# MPU.net
KiCad netlist of a schematic drawn in Altium Designer
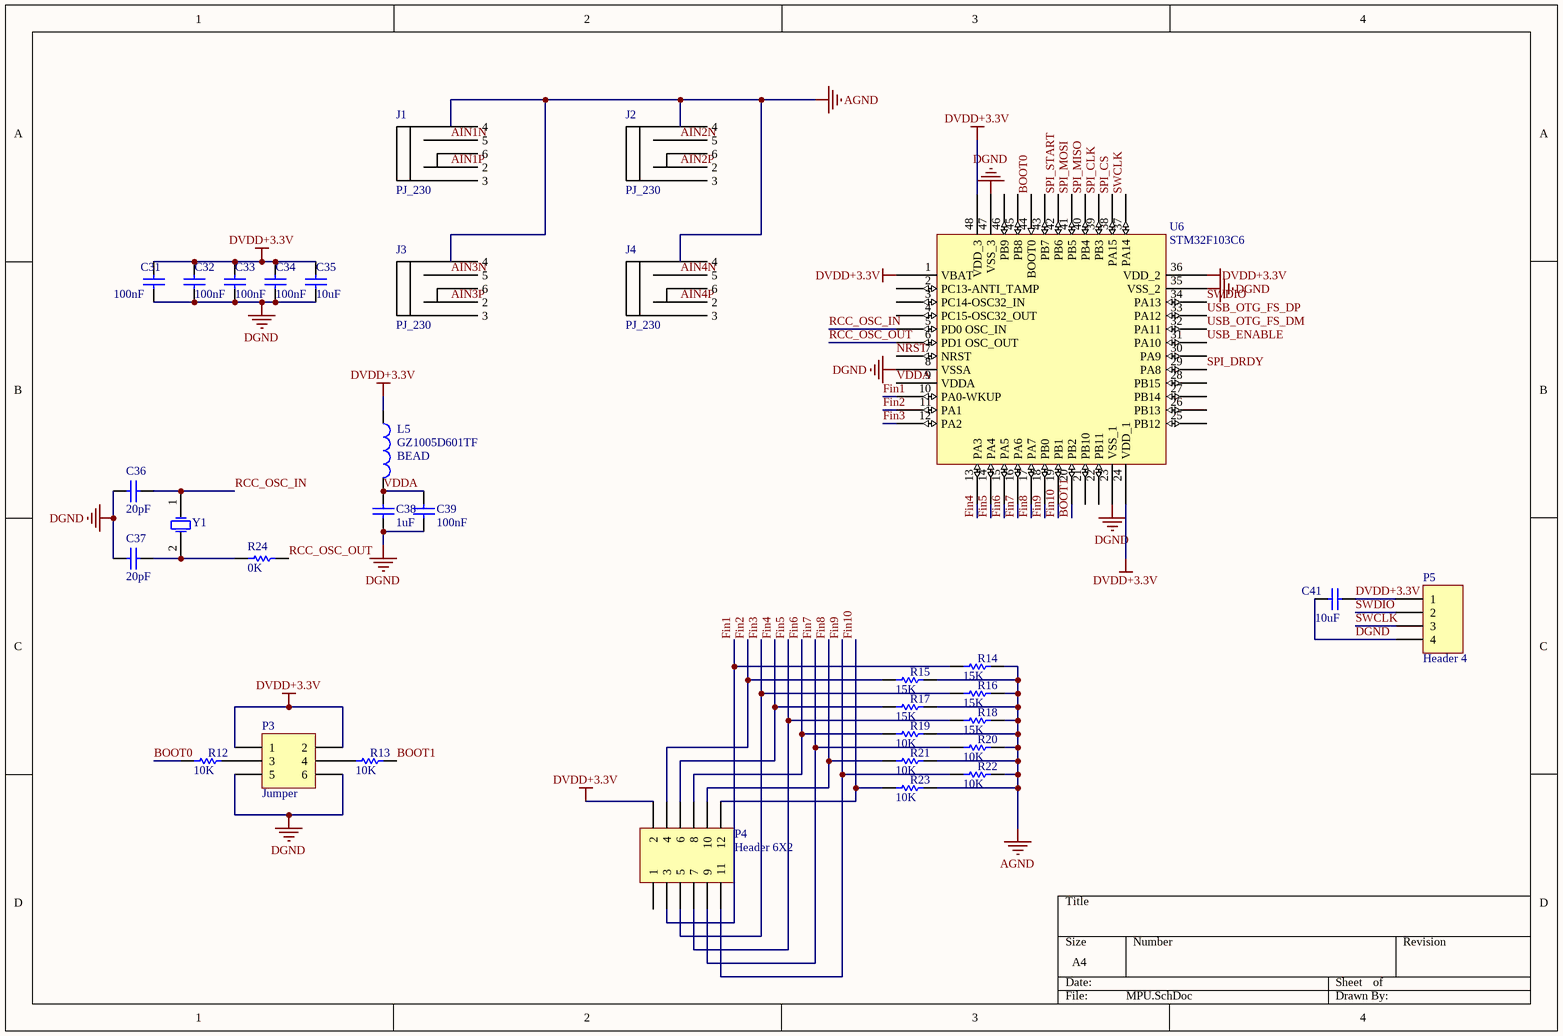
[diagram p0: MPU.SchDoc]

(export (version "E")
  (design (tool "Eeschema 10.0.6"))
  (components
    (comp (ref "C31")
      (value "100nF")
      (footprint "1608[0603]")
      (description "Capacitor")
      (fields (field (name "PUBLISHER") "Altium Limited"))
      (libsource (lib "Miscellaneous Devices") (part "Cap"))
    )
    (comp (ref "C32")
      (value "100nF")
      (footprint "1608[0603]")
      (description "Capacitor")
      (fields (field (name "PUBLISHER") "Altium Limited"))
      (libsource (lib "Miscellaneous Devices") (part "Cap"))
    )
    (comp (ref "C33")
      (value "100nF")
      (footprint "1608[0603]")
      (description "Capacitor")
      (fields (field (name "PUBLISHER") "Altium Limited"))
      (libsource (lib "Miscellaneous Devices") (part "Cap"))
    )
    (comp (ref "C34")
      (value "100nF")
      (footprint "1608[0603]")
      (description "Capacitor")
      (fields (field (name "PUBLISHER") "Altium Limited"))
      (libsource (lib "Miscellaneous Devices") (part "Cap"))
    )
    (comp (ref "C35")
      (value "10uF")
      (footprint "1608[0603]")
      (description "Capacitor")
      (fields (field (name "PUBLISHER") "Altium Limited"))
      (libsource (lib "Miscellaneous Devices") (part "Cap"))
    )
    (comp (ref "C36")
      (value "20pF")
      (footprint "1608[0603]")
      (description "Capacitor")
      (fields (field (name "PUBLISHER") "Altium Limited"))
      (libsource (lib "Miscellaneous Devices") (part "Cap"))
    )
    (comp (ref "C37")
      (value "20pF")
      (footprint "1608[0603]")
      (description "Capacitor")
      (fields (field (name "PUBLISHER") "Altium Limited"))
      (libsource (lib "Miscellaneous Devices") (part "Cap"))
    )
    (comp (ref "C38")
      (value "1uF")
      (footprint "1608[0603]")
      (description "Capacitor")
      (fields (field (name "PUBLISHER") "Altium Limited"))
      (libsource (lib "Miscellaneous Devices") (part "Cap"))
    )
    (comp (ref "C39")
      (value "100nF")
      (footprint "1608[0603]")
      (description "Capacitor")
      (fields (field (name "PUBLISHER") "Altium Limited"))
      (libsource (lib "Miscellaneous Devices") (part "Cap"))
    )
    (comp (ref "C41")
      (value "10uF")
      (footprint "1608[0603]")
      (description "Capacitor")
      (fields (field (name "PUBLISHER") "Altium Limited"))
      (libsource (lib "Miscellaneous Devices") (part "Cap"))
    )
    (comp (ref "J1")
      (value "PJ_230")
      (footprint "PJ_230")
      (description "Phone Jack")
      (libsource (lib "PJ_230") (part "PJ_230"))
    )
    (comp (ref "J2")
      (value "PJ_230")
      (footprint "PJ_230")
      (description "Phone Jack")
      (libsource (lib "PJ_230") (part "PJ_230"))
    )
    (comp (ref "J3")
      (value "PJ_230")
      (footprint "PJ_230")
      (description "Phone Jack")
      (libsource (lib "PJ_230") (part "PJ_230"))
    )
    (comp (ref "J4")
      (value "PJ_230")
      (footprint "PJ_230")
      (description "Phone Jack")
      (libsource (lib "PJ_230") (part "PJ_230"))
    )
    (comp (ref "L5")
      (value "GZ1005D601TF")
      (footprint "0402-A")
      (description "Inductor")
      (fields (field (name "PUBLISHER") "Altium Limited"))
      (libsource (lib "Miscellaneous Devices") (part "Inductor"))
    )
    (comp (ref "P3")
      (value "Jumper")
      (footprint "HDR2X3")
      (description "Header, 3-Pin, Dual row")
      (fields (field (name "PUBLISHER") "Altium Limited"))
      (libsource (lib "Miscellaneous Connectors") (part "Header 3X2"))
    )
    (comp (ref "P4")
      (value "Header 6X2")
      (footprint "HDR2X6")
      (description "Header, 6-Pin, Dual row")
      (fields (field (name "PUBLISHER") "Altium Limited"))
      (libsource (lib "Miscellaneous Connectors") (part "Header 6X2"))
    )
    (comp (ref "P5")
      (value "Header 4")
      (footprint "XH4")
      (description "Header, 4-Pin")
      (fields (field (name "PUBLISHER") "Altium Limited"))
      (libsource (lib "Miscellaneous Connectors") (part "Header 4"))
    )
    (comp (ref "R12")
      (value "10K")
      (footprint "J1-0603")
      (description "Resistor")
      (fields (field (name "PUBLISHER") "Altium Limited"))
      (libsource (lib "Miscellaneous Devices") (part "Res1"))
    )
    (comp (ref "R13")
      (value "10K")
      (footprint "J1-0603")
      (description "Resistor")
      (fields (field (name "PUBLISHER") "Altium Limited"))
      (libsource (lib "Miscellaneous Devices") (part "Res1"))
    )
    (comp (ref "R14")
      (value "15K")
      (footprint "J1-0603")
      (description "Resistor")
      (fields (field (name "PUBLISHER") "Altium Limited"))
      (libsource (lib "Miscellaneous Devices") (part "Res1"))
    )
    (comp (ref "R15")
      (value "15K")
      (footprint "J1-0603")
      (description "Resistor")
      (fields (field (name "PUBLISHER") "Altium Limited"))
      (libsource (lib "Miscellaneous Devices") (part "Res1"))
    )
    (comp (ref "R16")
      (value "15K")
      (footprint "J1-0603")
      (description "Resistor")
      (fields (field (name "PUBLISHER") "Altium Limited"))
      (libsource (lib "Miscellaneous Devices") (part "Res1"))
    )
    (comp (ref "R17")
      (value "15K")
      (footprint "J1-0603")
      (description "Resistor")
      (fields (field (name "PUBLISHER") "Altium Limited"))
      (libsource (lib "Miscellaneous Devices") (part "Res1"))
    )
    (comp (ref "R18")
      (value "15K")
      (footprint "J1-0603")
      (description "Resistor")
      (fields (field (name "PUBLISHER") "Altium Limited"))
      (libsource (lib "Miscellaneous Devices") (part "Res1"))
    )
    (comp (ref "R19")
      (value "10K")
      (footprint "J1-0603")
      (description "Resistor")
      (fields (field (name "PUBLISHER") "Altium Limited"))
      (libsource (lib "Miscellaneous Devices") (part "Res1"))
    )
    (comp (ref "R20")
      (value "10K")
      (footprint "J1-0603")
      (description "Resistor")
      (fields (field (name "PUBLISHER") "Altium Limited"))
      (libsource (lib "Miscellaneous Devices") (part "Res1"))
    )
    (comp (ref "R21")
      (value "10K")
      (footprint "J1-0603")
      (description "Resistor")
      (fields (field (name "PUBLISHER") "Altium Limited"))
      (libsource (lib "Miscellaneous Devices") (part "Res1"))
    )
    (comp (ref "R22")
      (value "10K")
      (footprint "J1-0603")
      (description "Resistor")
      (fields (field (name "PUBLISHER") "Altium Limited"))
      (libsource (lib "Miscellaneous Devices") (part "Res1"))
    )
    (comp (ref "R23")
      (value "10K")
      (footprint "J1-0603")
      (description "Resistor")
      (fields (field (name "PUBLISHER") "Altium Limited"))
      (libsource (lib "Miscellaneous Devices") (part "Res1"))
    )
    (comp (ref "R24")
      (value "0K")
      (footprint "J1-0603")
      (description "Resistor")
      (fields (field (name "PUBLISHER") "Altium Limited"))
      (libsource (lib "Miscellaneous Devices") (part "Res1"))
    )
    (comp (ref "U6")
      (value "STM32F103C6")
      (footprint "STM32F103C8T6")
      (description "IC MCU 32BIT 64KB FLASH 48LQFP")
      (libsource (lib "STM32F103C8T6") (part "STM32F103C8T6"))
    )
    (comp (ref "Y1")
      (value "XTAL")
      (footprint "Crystal_HCM49")
      (description "Crystal Oscillator")
      (fields (field (name "PUBLISHER") "Altium Limited"))
      (libsource (lib "Miscellaneous Devices") (part "XTAL"))
    )
  )
  (nets
    (net (code "1") (name "/AIN1N") (class "Default")
      (node (ref "J1") (pin "5") (pinfunction "5_5") (pintype "passive"))
    )
    (net (code "2") (name "/AIN1P") (class "Default")
      (node (ref "J1") (pin "2") (pinfunction "2_2") (pintype "passive"))
    )
    (net (code "3") (name "/AIN2N") (class "Default")
      (node (ref "J2") (pin "5") (pinfunction "5_5") (pintype "passive"))
    )
    (net (code "4") (name "/AIN2P") (class "Default")
      (node (ref "J2") (pin "2") (pinfunction "2_2") (pintype "passive"))
    )
    (net (code "5") (name "/AIN3N") (class "Default")
      (node (ref "J3") (pin "5") (pinfunction "5_5") (pintype "passive"))
    )
    (net (code "6") (name "/AIN3P") (class "Default")
      (node (ref "J3") (pin "2") (pinfunction "2_2") (pintype "passive"))
    )
    (net (code "7") (name "/AIN4N") (class "Default")
      (node (ref "J4") (pin "5") (pinfunction "5_5") (pintype "passive"))
    )
    (net (code "8") (name "/AIN4P") (class "Default")
      (node (ref "J4") (pin "2") (pinfunction "2_2") (pintype "passive"))
    )
    (net (code "9") (name "/BOOT0") (class "Default")
      (node (ref "R12") (pin "1") (pinfunction "1_1") (pintype "passive"))
      (node (ref "U6") (pin "44") (pinfunction "BOOT0_44") (pintype "input"))
    )
    (net (code "10") (name "/BOOT1") (class "Default")
      (node (ref "R13") (pin "2") (pinfunction "2_2") (pintype "passive"))
      (node (ref "U6") (pin "20") (pinfunction "PB2_20") (pintype "bidirectional"))
    )
    (net (code "11") (name "/Fin1") (class "Default")
      (node (ref "P4") (pin "3") (pinfunction "3_3") (pintype "passive"))
      (node (ref "R14") (pin "1") (pinfunction "1_1") (pintype "passive"))
      (node (ref "U6") (pin "10") (pinfunction "PA0-WKUP_10") (pintype "bidirectional"))
    )
    (net (code "12") (name "/Fin2") (class "Default")
      (node (ref "P4") (pin "4") (pinfunction "4_4") (pintype "passive"))
      (node (ref "R15") (pin "1") (pinfunction "1_1") (pintype "passive"))
      (node (ref "U6") (pin "11") (pinfunction "PA1_11") (pintype "bidirectional"))
    )
    (net (code "13") (name "/Fin3") (class "Default")
      (node (ref "P4") (pin "5") (pinfunction "5_5") (pintype "passive"))
      (node (ref "R16") (pin "1") (pinfunction "1_1") (pintype "passive"))
      (node (ref "U6") (pin "12") (pinfunction "PA2_12") (pintype "bidirectional"))
    )
    (net (code "14") (name "/Fin4") (class "Default")
      (node (ref "P4") (pin "6") (pinfunction "6_6") (pintype "passive"))
      (node (ref "R17") (pin "1") (pinfunction "1_1") (pintype "passive"))
      (node (ref "U6") (pin "13") (pinfunction "PA3_13") (pintype "bidirectional"))
    )
    (net (code "15") (name "/Fin5") (class "Default")
      (node (ref "P4") (pin "7") (pinfunction "7_7") (pintype "passive"))
      (node (ref "R18") (pin "1") (pinfunction "1_1") (pintype "passive"))
      (node (ref "U6") (pin "14") (pinfunction "PA4_14") (pintype "bidirectional"))
    )
    (net (code "16") (name "/Fin6") (class "Default")
      (node (ref "P4") (pin "8") (pinfunction "8_8") (pintype "passive"))
      (node (ref "R19") (pin "1") (pinfunction "1_1") (pintype "passive"))
      (node (ref "U6") (pin "15") (pinfunction "PA5_15") (pintype "bidirectional"))
    )
    (net (code "17") (name "/Fin7") (class "Default")
      (node (ref "P4") (pin "9") (pinfunction "9_9") (pintype "passive"))
      (node (ref "R20") (pin "1") (pinfunction "1_1") (pintype "passive"))
      (node (ref "U6") (pin "16") (pinfunction "PA6_16") (pintype "bidirectional"))
    )
    (net (code "18") (name "/Fin8") (class "Default")
      (node (ref "P4") (pin "10") (pinfunction "10_10") (pintype "passive"))
      (node (ref "R21") (pin "1") (pinfunction "1_1") (pintype "passive"))
      (node (ref "U6") (pin "17") (pinfunction "PA7_17") (pintype "bidirectional"))
    )
    (net (code "19") (name "/Fin9") (class "Default")
      (node (ref "P4") (pin "11") (pinfunction "11_11") (pintype "passive"))
      (node (ref "R22") (pin "1") (pinfunction "1_1") (pintype "passive"))
      (node (ref "U6") (pin "18") (pinfunction "PB0_18") (pintype "bidirectional"))
    )
    (net (code "20") (name "/Fin10") (class "Default")
      (node (ref "P4") (pin "12") (pinfunction "12_12") (pintype "passive"))
      (node (ref "R23") (pin "1") (pinfunction "1_1") (pintype "passive"))
      (node (ref "U6") (pin "19") (pinfunction "PB1_19") (pintype "bidirectional"))
    )
    (net (code "21") (name "/NRST") (class "Default")
      (node (ref "U6") (pin "7") (pinfunction "NRST_7") (pintype "bidirectional"))
    )
    (net (code "22") (name "/RCC_OSC_IN") (class "Default")
      (node (ref "C36") (pin "2") (pinfunction "2_2") (pintype "passive"))
      (node (ref "U6") (pin "5") (pinfunction "PD0_OSC_IN_5") (pintype "bidirectional"))
      (node (ref "Y1") (pin "1") (pinfunction "OSC1_1") (pintype "passive"))
    )
    (net (code "23") (name "/RCC_OSC_OUT") (class "Default")
      (node (ref "R24") (pin "2") (pinfunction "2_2") (pintype "passive"))
      (node (ref "U6") (pin "6") (pinfunction "PD1_OSC_OUT_6") (pintype "bidirectional"))
    )
    (net (code "24") (name "/SPI_CLK") (class "Default")
      (node (ref "U6") (pin "39") (pinfunction "PB3_39") (pintype "bidirectional"))
    )
    (net (code "25") (name "/SPI_CS") (class "Default")
      (node (ref "U6") (pin "38") (pinfunction "PA15_38") (pintype "bidirectional"))
    )
    (net (code "26") (name "/SPI_DRDY") (class "Default")
      (node (ref "U6") (pin "29") (pinfunction "PA8_29") (pintype "bidirectional"))
    )
    (net (code "27") (name "/SPI_MISO") (class "Default")
      (node (ref "U6") (pin "40") (pinfunction "PB4_40") (pintype "bidirectional"))
    )
    (net (code "28") (name "/SPI_MOSI") (class "Default")
      (node (ref "U6") (pin "41") (pinfunction "PB5_41") (pintype "bidirectional"))
    )
    (net (code "29") (name "/SPI_START") (class "Default")
      (node (ref "U6") (pin "42") (pinfunction "PB6_42") (pintype "bidirectional"))
    )
    (net (code "30") (name "/SWCLK") (class "Default")
      (node (ref "P5") (pin "3") (pinfunction "3_3") (pintype "passive"))
      (node (ref "U6") (pin "37") (pinfunction "PA14_37") (pintype "bidirectional"))
    )
    (net (code "31") (name "/SWDIO") (class "Default")
      (node (ref "P5") (pin "2") (pinfunction "2_2") (pintype "passive"))
      (node (ref "U6") (pin "34") (pinfunction "PA13_34") (pintype "bidirectional"))
    )
    (net (code "32") (name "/USB_ENABLE") (class "Default")
      (node (ref "U6") (pin "31") (pinfunction "PA10_31") (pintype "bidirectional"))
    )
    (net (code "33") (name "/USB_OTG_FS_DM") (class "Default")
      (node (ref "U6") (pin "32") (pinfunction "PA11_32") (pintype "bidirectional"))
    )
    (net (code "34") (name "/USB_OTG_FS_DP") (class "Default")
      (node (ref "U6") (pin "33") (pinfunction "PA12_33") (pintype "bidirectional"))
    )
    (net (code "35") (name "/VDDA") (class "Default")
      (node (ref "C38") (pin "2") (pinfunction "2_2") (pintype "passive"))
      (node (ref "C39") (pin "2") (pinfunction "2_2") (pintype "passive"))
      (node (ref "L5") (pin "2") (pinfunction "2_2") (pintype "passive"))
      (node (ref "U6") (pin "9") (pinfunction "VDDA_9") (pintype "power_in"))
    )
    (net (code "36") (name "AGND") (class "Default")
      (node (ref "J1") (pin "4") (pinfunction "4_4") (pintype "passive"))
      (node (ref "J2") (pin "4") (pinfunction "4_4") (pintype "passive"))
      (node (ref "J3") (pin "4") (pinfunction "4_4") (pintype "passive"))
      (node (ref "J4") (pin "4") (pinfunction "4_4") (pintype "passive"))
      (node (ref "R14") (pin "2") (pinfunction "2_2") (pintype "passive"))
      (node (ref "R15") (pin "2") (pinfunction "2_2") (pintype "passive"))
      (node (ref "R16") (pin "2") (pinfunction "2_2") (pintype "passive"))
      (node (ref "R17") (pin "2") (pinfunction "2_2") (pintype "passive"))
      (node (ref "R18") (pin "2") (pinfunction "2_2") (pintype "passive"))
      (node (ref "R19") (pin "2") (pinfunction "2_2") (pintype "passive"))
      (node (ref "R20") (pin "2") (pinfunction "2_2") (pintype "passive"))
      (node (ref "R21") (pin "2") (pinfunction "2_2") (pintype "passive"))
      (node (ref "R22") (pin "2") (pinfunction "2_2") (pintype "passive"))
      (node (ref "R23") (pin "2") (pinfunction "2_2") (pintype "passive"))
    )
    (net (code "37") (name "DGND") (class "Default")
      (node (ref "C31") (pin "1") (pinfunction "1_1") (pintype "passive"))
      (node (ref "C32") (pin "1") (pinfunction "1_1") (pintype "passive"))
      (node (ref "C33") (pin "1") (pinfunction "1_1") (pintype "passive"))
      (node (ref "C34") (pin "1") (pinfunction "1_1") (pintype "passive"))
      (node (ref "C35") (pin "1") (pinfunction "1_1") (pintype "passive"))
      (node (ref "C36") (pin "1") (pinfunction "1_1") (pintype "passive"))
      (node (ref "C37") (pin "1") (pinfunction "1_1") (pintype "passive"))
      (node (ref "C38") (pin "1") (pinfunction "1_1") (pintype "passive"))
      (node (ref "C39") (pin "1") (pinfunction "1_1") (pintype "passive"))
      (node (ref "C41") (pin "1") (pinfunction "1_1") (pintype "passive"))
      (node (ref "P3") (pin "5") (pinfunction "5_5") (pintype "passive"))
      (node (ref "P3") (pin "6") (pinfunction "6_6") (pintype "passive"))
      (node (ref "P5") (pin "4") (pinfunction "4_4") (pintype "passive"))
      (node (ref "U6") (pin "23") (pinfunction "VSS_1_23") (pintype "power_in"))
      (node (ref "U6") (pin "35") (pinfunction "VSS_2_35") (pintype "power_in"))
      (node (ref "U6") (pin "47") (pinfunction "VSS_3_47") (pintype "power_in"))
      (node (ref "U6") (pin "8") (pinfunction "VSSA_8") (pintype "power_in"))
    )
    (net (code "38") (name "DVDD+3.3V") (class "Default")
      (node (ref "C31") (pin "2") (pinfunction "2_2") (pintype "passive"))
      (node (ref "C32") (pin "2") (pinfunction "2_2") (pintype "passive"))
      (node (ref "C33") (pin "2") (pinfunction "2_2") (pintype "passive"))
      (node (ref "C34") (pin "2") (pinfunction "2_2") (pintype "passive"))
      (node (ref "C35") (pin "2") (pinfunction "2_2") (pintype "passive"))
      (node (ref "C41") (pin "2") (pinfunction "2_2") (pintype "passive"))
      (node (ref "L5") (pin "1") (pinfunction "1_1") (pintype "passive"))
      (node (ref "P3") (pin "1") (pinfunction "1_1") (pintype "passive"))
      (node (ref "P3") (pin "2") (pinfunction "2_2") (pintype "passive"))
      (node (ref "P4") (pin "2") (pinfunction "2_2") (pintype "passive"))
      (node (ref "P5") (pin "1") (pinfunction "1_1") (pintype "passive"))
      (node (ref "U6") (pin "1") (pinfunction "VBAT_1") (pintype "passive"))
      (node (ref "U6") (pin "24") (pinfunction "VDD_1_24") (pintype "power_in"))
      (node (ref "U6") (pin "36") (pinfunction "VDD_2_36") (pintype "power_in"))
      (node (ref "U6") (pin "48") (pinfunction "VDD_3_48") (pintype "power_in"))
    )
    (net (code "39") (name "Net-(P3-Pad3)") (class "Default")
      (node (ref "P3") (pin "3") (pinfunction "3_3") (pintype "passive"))
      (node (ref "R12") (pin "2") (pinfunction "2_2") (pintype "passive"))
    )
    (net (code "40") (name "Net-(P3-Pad4)") (class "Default")
      (node (ref "P3") (pin "4") (pinfunction "4_4") (pintype "passive"))
      (node (ref "R13") (pin "1") (pinfunction "1_1") (pintype "passive"))
    )
    (net (code "41") (name "Net-(Y1-OSC2)") (class "Default")
      (node (ref "C37") (pin "2") (pinfunction "2_2") (pintype "passive"))
      (node (ref "R24") (pin "1") (pinfunction "1_1") (pintype "passive"))
      (node (ref "Y1") (pin "2") (pinfunction "OSC2_2") (pintype "passive"))
    )
    (net (code "42") (name "unconnected-(J1-Pad3)") (class "Default")
      (node (ref "J1") (pin "3") (pinfunction "3_3") (pintype "passive"))
    )
    (net (code "43") (name "unconnected-(J1-Pad6)") (class "Default")
      (node (ref "J1") (pin "6") (pinfunction "6_6") (pintype "passive"))
    )
    (net (code "44") (name "unconnected-(J2-Pad3)") (class "Default")
      (node (ref "J2") (pin "3") (pinfunction "3_3") (pintype "passive"))
    )
    (net (code "45") (name "unconnected-(J2-Pad6)") (class "Default")
      (node (ref "J2") (pin "6") (pinfunction "6_6") (pintype "passive"))
    )
    (net (code "46") (name "unconnected-(J3-Pad3)") (class "Default")
      (node (ref "J3") (pin "3") (pinfunction "3_3") (pintype "passive"))
    )
    (net (code "47") (name "unconnected-(J3-Pad6)") (class "Default")
      (node (ref "J3") (pin "6") (pinfunction "6_6") (pintype "passive"))
    )
    (net (code "48") (name "unconnected-(J4-Pad3)") (class "Default")
      (node (ref "J4") (pin "3") (pinfunction "3_3") (pintype "passive"))
    )
    (net (code "49") (name "unconnected-(J4-Pad6)") (class "Default")
      (node (ref "J4") (pin "6") (pinfunction "6_6") (pintype "passive"))
    )
    (net (code "50") (name "unconnected-(P4-Pad1)") (class "Default")
      (node (ref "P4") (pin "1") (pinfunction "1_1") (pintype "passive"))
    )
    (net (code "51") (name "unconnected-(U6-PA9-Pad30)") (class "Default")
      (node (ref "U6") (pin "30") (pinfunction "PA9_30") (pintype "bidirectional"))
    )
    (net (code "52") (name "unconnected-(U6-PB7-Pad43)") (class "Default")
      (node (ref "U6") (pin "43") (pinfunction "PB7_43") (pintype "bidirectional"))
    )
    (net (code "53") (name "unconnected-(U6-PB8-Pad45)") (class "Default")
      (node (ref "U6") (pin "45") (pinfunction "PB8_45") (pintype "bidirectional"))
    )
    (net (code "54") (name "unconnected-(U6-PB9-Pad46)") (class "Default")
      (node (ref "U6") (pin "46") (pinfunction "PB9_46") (pintype "bidirectional"))
    )
    (net (code "55") (name "unconnected-(U6-PB10-Pad21)") (class "Default")
      (node (ref "U6") (pin "21") (pinfunction "PB10_21") (pintype "bidirectional"))
    )
    (net (code "56") (name "unconnected-(U6-PB11-Pad22)") (class "Default")
      (node (ref "U6") (pin "22") (pinfunction "PB11_22") (pintype "bidirectional"))
    )
    (net (code "57") (name "unconnected-(U6-PB12-Pad25)") (class "Default")
      (node (ref "U6") (pin "25") (pinfunction "PB12_25") (pintype "bidirectional"))
    )
    (net (code "58") (name "unconnected-(U6-PB13-Pad26)") (class "Default")
      (node (ref "U6") (pin "26") (pinfunction "PB13_26") (pintype "bidirectional"))
    )
    (net (code "59") (name "unconnected-(U6-PB14-Pad27)") (class "Default")
      (node (ref "U6") (pin "27") (pinfunction "PB14_27") (pintype "bidirectional"))
    )
    (net (code "60") (name "unconnected-(U6-PB15-Pad28)") (class "Default")
      (node (ref "U6") (pin "28") (pinfunction "PB15_28") (pintype "bidirectional"))
    )
    (net (code "61") (name "unconnected-(U6-PC13-ANTI_TAMP-Pad2)") (class "Default")
      (node (ref "U6") (pin "2") (pinfunction "PC13-ANTI_TAMP_2") (pintype "bidirectional"))
    )
    (net (code "62") (name "unconnected-(U6-PC14-OSC32_IN-Pad3)") (class "Default")
      (node (ref "U6") (pin "3") (pinfunction "PC14-OSC32_IN_3") (pintype "bidirectional"))
    )
    (net (code "63") (name "unconnected-(U6-PC15-OSC32_OUT-Pad4)") (class "Default")
      (node (ref "U6") (pin "4") (pinfunction "PC15-OSC32_OUT_4") (pintype "bidirectional"))
    )
  )
)
